# PiCal.net
KiCad netlist of a schematic drawn in EAGLE
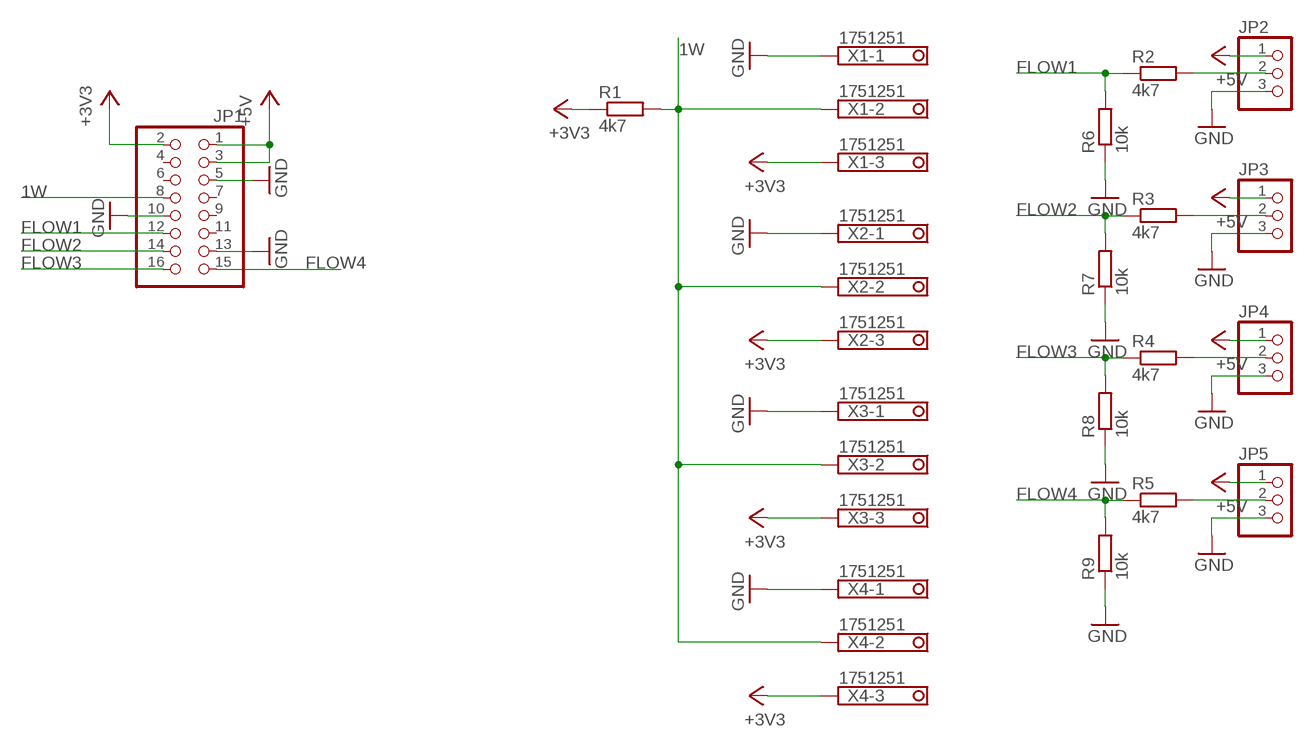
[diagram p0: schematic, sheet 1]

(export (version "E")
  (design (tool "Eeschema 10.0.6"))
  (components
    (comp (ref "JP1")
      (value "PINHD-2X8")
      (footprint "eagle-import:2X08")
      (libsource (lib "eagle-import") (part "PINHD-2X8"))
    )
    (comp (ref "JP2")
      (value "PINHD-1X3")
      (footprint "eagle-import:1X03")
      (libsource (lib "eagle-import") (part "PINHD-1X3"))
    )
    (comp (ref "JP3")
      (value "PINHD-1X3")
      (footprint "eagle-import:1X03")
      (libsource (lib "eagle-import") (part "PINHD-1X3"))
    )
    (comp (ref "JP4")
      (value "PINHD-1X3")
      (footprint "eagle-import:1X03")
      (libsource (lib "eagle-import") (part "PINHD-1X3"))
    )
    (comp (ref "JP5")
      (value "PINHD-1X3")
      (footprint "eagle-import:1X03")
      (libsource (lib "eagle-import") (part "PINHD-1X3"))
    )
    (comp (ref "R1")
      (value "4k7")
      (footprint "eagle-import:M0805")
      (libsource (lib "eagle-import") (part "R-EU_M0805"))
    )
    (comp (ref "R2")
      (value "4k7")
      (footprint "eagle-import:M0805")
      (libsource (lib "eagle-import") (part "R-EU_M0805"))
    )
    (comp (ref "R3")
      (value "4k7")
      (footprint "eagle-import:M0805")
      (libsource (lib "eagle-import") (part "R-EU_M0805"))
    )
    (comp (ref "R4")
      (value "4k7")
      (footprint "eagle-import:M0805")
      (libsource (lib "eagle-import") (part "R-EU_M0805"))
    )
    (comp (ref "R5")
      (value "4k7")
      (footprint "eagle-import:M0805")
      (libsource (lib "eagle-import") (part "R-EU_M0805"))
    )
    (comp (ref "R6")
      (value "10k")
      (footprint "eagle-import:M0805")
      (libsource (lib "eagle-import") (part "R-EU_M0805"))
    )
    (comp (ref "R7")
      (value "10k")
      (footprint "eagle-import:M0805")
      (libsource (lib "eagle-import") (part "R-EU_M0805"))
    )
    (comp (ref "R8")
      (value "10k")
      (footprint "eagle-import:M0805")
      (libsource (lib "eagle-import") (part "R-EU_M0805"))
    )
    (comp (ref "R9")
      (value "10k")
      (footprint "eagle-import:M0805")
      (libsource (lib "eagle-import") (part "R-EU_M0805"))
    )
    (comp (ref "X1")
      (value "1751251")
      (footprint "eagle-import:1751251")
      (libsource (lib "eagle-import") (part "1751251"))
    )
    (comp (ref "X2")
      (value "1751251")
      (footprint "eagle-import:1751251")
      (libsource (lib "eagle-import") (part "1751251"))
    )
    (comp (ref "X3")
      (value "1751251")
      (footprint "eagle-import:1751251")
      (libsource (lib "eagle-import") (part "1751251"))
    )
    (comp (ref "X4")
      (value "1751251")
      (footprint "eagle-import:1751251")
      (libsource (lib "eagle-import") (part "1751251"))
    )
  )
  (nets
    (net (code "1") (name "+3V3") (class "Default")
      (node (ref "JP1") (pin "2") (pinfunction "2_2") (pintype "passive"))
      (node (ref "R1") (pin "1") (pinfunction "1_1") (pintype "passive"))
      (node (ref "X1") (pin "3") (pinfunction "K_3") (pintype "passive"))
      (node (ref "X2") (pin "3") (pinfunction "K_3") (pintype "passive"))
      (node (ref "X3") (pin "3") (pinfunction "K_3") (pintype "passive"))
      (node (ref "X4") (pin "3") (pinfunction "K_3") (pintype "passive"))
    )
    (net (code "2") (name "+5V") (class "Default")
      (node (ref "JP1") (pin "1") (pinfunction "1_1") (pintype "passive"))
      (node (ref "JP1") (pin "3") (pinfunction "3_3") (pintype "passive"))
      (node (ref "JP2") (pin "1") (pinfunction "1_1") (pintype "passive"))
      (node (ref "JP3") (pin "1") (pinfunction "1_1") (pintype "passive"))
      (node (ref "JP4") (pin "1") (pinfunction "1_1") (pintype "passive"))
      (node (ref "JP5") (pin "1") (pinfunction "1_1") (pintype "passive"))
    )
    (net (code "3") (name "/1W") (class "Default")
      (node (ref "JP1") (pin "8") (pinfunction "8_8") (pintype "passive"))
      (node (ref "R1") (pin "2") (pinfunction "2_2") (pintype "passive"))
      (node (ref "X1") (pin "2") (pinfunction "K_2") (pintype "passive"))
      (node (ref "X2") (pin "2") (pinfunction "K_2") (pintype "passive"))
      (node (ref "X3") (pin "2") (pinfunction "K_2") (pintype "passive"))
      (node (ref "X4") (pin "2") (pinfunction "K_2") (pintype "passive"))
    )
    (net (code "4") (name "/FLOW1") (class "Default")
      (node (ref "JP1") (pin "12") (pinfunction "12_12") (pintype "passive"))
      (node (ref "R2") (pin "1") (pinfunction "1_1") (pintype "passive"))
      (node (ref "R6") (pin "2") (pinfunction "2_2") (pintype "passive"))
    )
    (net (code "5") (name "/FLOW2") (class "Default")
      (node (ref "JP1") (pin "14") (pinfunction "14_14") (pintype "passive"))
      (node (ref "R3") (pin "1") (pinfunction "1_1") (pintype "passive"))
      (node (ref "R7") (pin "2") (pinfunction "2_2") (pintype "passive"))
    )
    (net (code "6") (name "/FLOW3") (class "Default")
      (node (ref "JP1") (pin "16") (pinfunction "16_16") (pintype "passive"))
      (node (ref "R4") (pin "1") (pinfunction "1_1") (pintype "passive"))
      (node (ref "R8") (pin "2") (pinfunction "2_2") (pintype "passive"))
    )
    (net (code "7") (name "/FLOW4") (class "Default")
      (node (ref "JP1") (pin "15") (pinfunction "15_15") (pintype "passive"))
      (node (ref "R5") (pin "1") (pinfunction "1_1") (pintype "passive"))
      (node (ref "R9") (pin "2") (pinfunction "2_2") (pintype "passive"))
    )
    (net (code "8") (name "GND") (class "Default")
      (node (ref "JP1") (pin "10") (pinfunction "10_10") (pintype "passive"))
      (node (ref "JP1") (pin "13") (pinfunction "13_13") (pintype "passive"))
      (node (ref "JP1") (pin "5") (pinfunction "5_5") (pintype "passive"))
      (node (ref "JP2") (pin "3") (pinfunction "3_3") (pintype "passive"))
      (node (ref "JP3") (pin "3") (pinfunction "3_3") (pintype "passive"))
      (node (ref "JP4") (pin "3") (pinfunction "3_3") (pintype "passive"))
      (node (ref "JP5") (pin "3") (pinfunction "3_3") (pintype "passive"))
      (node (ref "R6") (pin "1") (pinfunction "1_1") (pintype "passive"))
      (node (ref "R7") (pin "1") (pinfunction "1_1") (pintype "passive"))
      (node (ref "R8") (pin "1") (pinfunction "1_1") (pintype "passive"))
      (node (ref "R9") (pin "1") (pinfunction "1_1") (pintype "passive"))
      (node (ref "X1") (pin "1") (pinfunction "K_1") (pintype "passive"))
      (node (ref "X2") (pin "1") (pinfunction "K_1") (pintype "passive"))
      (node (ref "X3") (pin "1") (pinfunction "K_1") (pintype "passive"))
      (node (ref "X4") (pin "1") (pinfunction "K_1") (pintype "passive"))
    )
    (net (code "9") (name "Net-(JP2-Pad2)") (class "Default")
      (node (ref "JP2") (pin "2") (pinfunction "2_2") (pintype "passive"))
      (node (ref "R2") (pin "2") (pinfunction "2_2") (pintype "passive"))
    )
    (net (code "10") (name "Net-(JP3-Pad2)") (class "Default")
      (node (ref "JP3") (pin "2") (pinfunction "2_2") (pintype "passive"))
      (node (ref "R3") (pin "2") (pinfunction "2_2") (pintype "passive"))
    )
    (net (code "11") (name "Net-(JP4-Pad2)") (class "Default")
      (node (ref "JP4") (pin "2") (pinfunction "2_2") (pintype "passive"))
      (node (ref "R4") (pin "2") (pinfunction "2_2") (pintype "passive"))
    )
    (net (code "12") (name "Net-(JP5-Pad2)") (class "Default")
      (node (ref "JP5") (pin "2") (pinfunction "2_2") (pintype "passive"))
      (node (ref "R5") (pin "2") (pinfunction "2_2") (pintype "passive"))
    )
    (net (code "13") (name "unconnected-(JP1-Pad4)") (class "Default")
      (node (ref "JP1") (pin "4") (pinfunction "4_4") (pintype "passive"))
    )
    (net (code "14") (name "unconnected-(JP1-Pad6)") (class "Default")
      (node (ref "JP1") (pin "6") (pinfunction "6_6") (pintype "passive"))
    )
    (net (code "15") (name "unconnected-(JP1-Pad7)") (class "Default")
      (node (ref "JP1") (pin "7") (pinfunction "7_7") (pintype "passive"))
    )
    (net (code "16") (name "unconnected-(JP1-Pad9)") (class "Default")
      (node (ref "JP1") (pin "9") (pinfunction "9_9") (pintype "passive"))
    )
    (net (code "17") (name "unconnected-(JP1-Pad11)") (class "Default")
      (node (ref "JP1") (pin "11") (pinfunction "11_11") (pintype "passive"))
    )
  )
)
